# 05_SDRAM.net
KiCad netlist of a schematic drawn in Altium Designer
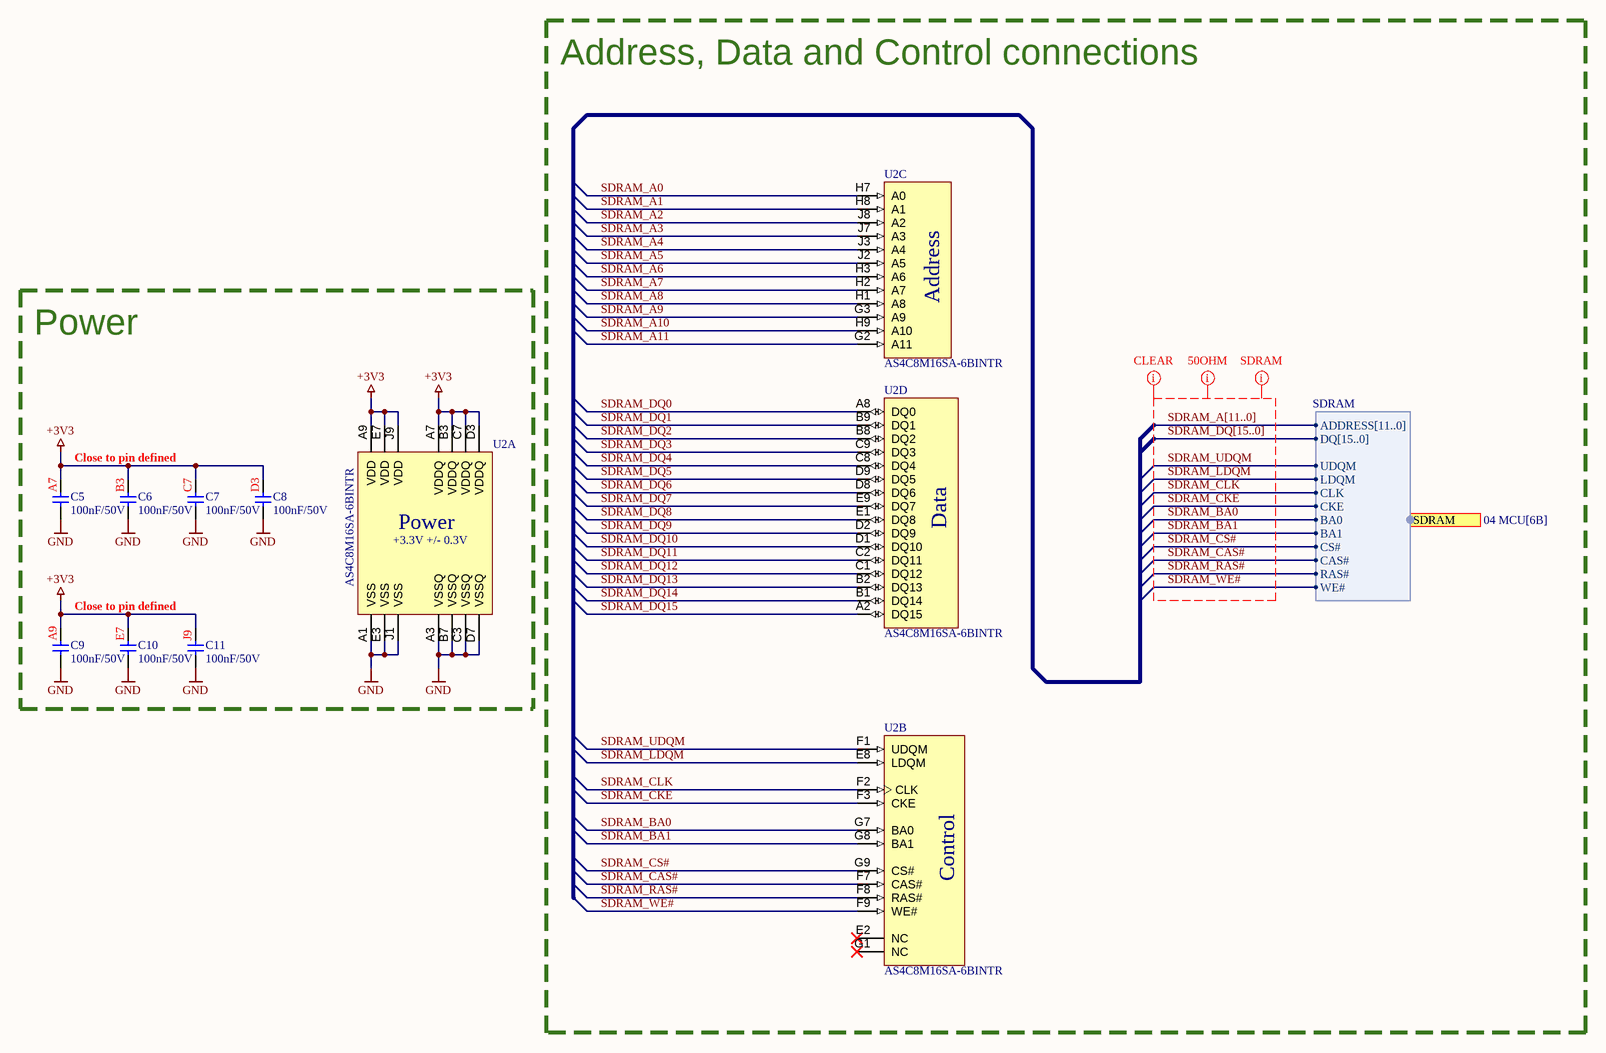
[diagram p0: 05 SDRAM.SchDoc]

(export (version "E")
  (design (tool "Eeschema 10.0.6"))
  (components
    (comp (ref "C5")
      (value "100nF/50V")
      (footprint "CAPC1005X06M-0402")
      (description "0.1 µF ±10% 50V Ceramic Capacitor X7R 0402 (1005 Metric)")
      (fields (field (name "MPN") "GRM155R71H104KE14D"))
      (libsource (lib "Symbol") (part "GRM155R71H104KE14D"))
    )
    (comp (ref "C6")
      (value "100nF/50V")
      (footprint "CAPC1005X06M-0402")
      (description "0.1 µF ±10% 50V Ceramic Capacitor X7R 0402 (1005 Metric)")
      (fields (field (name "MPN") "GRM155R71H104KE14D"))
      (libsource (lib "Symbol") (part "GRM155R71H104KE14D"))
    )
    (comp (ref "C7")
      (value "100nF/50V")
      (footprint "CAPC1005X06M-0402")
      (description "0.1 µF ±10% 50V Ceramic Capacitor X7R 0402 (1005 Metric)")
      (fields (field (name "MPN") "GRM155R71H104KE14D"))
      (libsource (lib "Symbol") (part "GRM155R71H104KE14D"))
    )
    (comp (ref "C8")
      (value "100nF/50V")
      (footprint "CAPC1005X06M-0402")
      (description "0.1 µF ±10% 50V Ceramic Capacitor X7R 0402 (1005 Metric)")
      (fields (field (name "MPN") "GRM155R71H104KE14D"))
      (libsource (lib "Symbol") (part "GRM155R71H104KE14D"))
    )
    (comp (ref "C9")
      (value "100nF/50V")
      (footprint "CAPC1005X06M-0402")
      (description "0.1 µF ±10% 50V Ceramic Capacitor X7R 0402 (1005 Metric)")
      (fields (field (name "MPN") "GRM155R71H104KE14D"))
      (libsource (lib "Symbol") (part "GRM155R71H104KE14D"))
    )
    (comp (ref "C10")
      (value "100nF/50V")
      (footprint "CAPC1005X06M-0402")
      (description "0.1 µF ±10% 50V Ceramic Capacitor X7R 0402 (1005 Metric)")
      (fields (field (name "MPN") "GRM155R71H104KE14D"))
      (libsource (lib "Symbol") (part "GRM155R71H104KE14D"))
    )
    (comp (ref "C11")
      (value "100nF/50V")
      (footprint "CAPC1005X06M-0402")
      (description "0.1 µF ±10% 50V Ceramic Capacitor X7R 0402 (1005 Metric)")
      (fields (field (name "MPN") "GRM155R71H104KE14D"))
      (libsource (lib "Symbol") (part "GRM155R71H104KE14D"))
    )
    (comp (ref "U2")
      (value "AS4C8M16SA-6BINTR")
      (footprint "TFBGA-54")
      (description "SDRAM Memory IC 128Mbit Parallel 166 MHz 5 ns 54-TFBGA (8x8)")
      (libsource (lib "Symbol") (part "AS4C8M16SA-6BINTR"))
    )
  )
  (nets
    (net (code "2") (name "+3V3") (class "Default")
      (node (ref "C10") (pin "2") (pinfunction "2_2") (pintype "passive"))
      (node (ref "C11") (pin "2") (pinfunction "2_2") (pintype "passive"))
      (node (ref "C5") (pin "2") (pinfunction "2_2") (pintype "passive"))
      (node (ref "C6") (pin "2") (pinfunction "2_2") (pintype "passive"))
      (node (ref "C7") (pin "2") (pinfunction "2_2") (pintype "passive"))
      (node (ref "C8") (pin "2") (pinfunction "2_2") (pintype "passive"))
      (node (ref "C9") (pin "2") (pinfunction "2_2") (pintype "passive"))
      (node (ref "U2") (pin "A7") (pinfunction "VDDQ_A7") (pintype "power_in"))
      (node (ref "U2") (pin "A9") (pinfunction "VDD_A9") (pintype "power_in"))
      (node (ref "U2") (pin "B3") (pinfunction "VDDQ_B3") (pintype "power_in"))
      (node (ref "U2") (pin "C7") (pinfunction "VDDQ_C7") (pintype "power_in"))
      (node (ref "U2") (pin "D3") (pinfunction "VDDQ_D3") (pintype "power_in"))
      (node (ref "U2") (pin "E7") (pinfunction "VDD_E7") (pintype "power_in"))
      (node (ref "U2") (pin "J9") (pinfunction "VDD_J9") (pintype "power_in"))
    )
    (net (code "3") (name "/SDRAM_A0") (class "Default")
      (node (ref "U2") (pin "H7") (pinfunction "A0_H7") (pintype "input"))
    )
    (net (code "4") (name "/SDRAM_A1") (class "Default")
      (node (ref "U2") (pin "H8") (pinfunction "A1_H8") (pintype "input"))
    )
    (net (code "5") (name "/SDRAM_A2") (class "Default")
      (node (ref "U2") (pin "J8") (pinfunction "A2_J8") (pintype "input"))
    )
    (net (code "6") (name "/SDRAM_A3") (class "Default")
      (node (ref "U2") (pin "J7") (pinfunction "A3_J7") (pintype "input"))
    )
    (net (code "7") (name "/SDRAM_A4") (class "Default")
      (node (ref "U2") (pin "J3") (pinfunction "A4_J3") (pintype "input"))
    )
    (net (code "8") (name "/SDRAM_A5") (class "Default")
      (node (ref "U2") (pin "J2") (pinfunction "A5_J2") (pintype "input"))
    )
    (net (code "9") (name "/SDRAM_A6") (class "Default")
      (node (ref "U2") (pin "H3") (pinfunction "A6_H3") (pintype "input"))
    )
    (net (code "10") (name "/SDRAM_A7") (class "Default")
      (node (ref "U2") (pin "H2") (pinfunction "A7_H2") (pintype "input"))
    )
    (net (code "11") (name "/SDRAM_A8") (class "Default")
      (node (ref "U2") (pin "H1") (pinfunction "A8_H1") (pintype "input"))
    )
    (net (code "12") (name "/SDRAM_A9") (class "Default")
      (node (ref "U2") (pin "G3") (pinfunction "A9_G3") (pintype "input"))
    )
    (net (code "13") (name "/SDRAM_A10") (class "Default")
      (node (ref "U2") (pin "H9") (pinfunction "A10_H9") (pintype "input"))
    )
    (net (code "14") (name "/SDRAM_A11") (class "Default")
      (node (ref "U2") (pin "G2") (pinfunction "A11_G2") (pintype "input"))
    )
    (net (code "15") (name "/SDRAM_BA0") (class "Default")
      (node (ref "U2") (pin "G7") (pinfunction "BA0_G7") (pintype "input"))
    )
    (net (code "16") (name "/SDRAM_BA1") (class "Default")
      (node (ref "U2") (pin "G8") (pinfunction "BA1_G8") (pintype "input"))
    )
    (net (code "17") (name "/SDRAM_CAS#") (class "Default")
      (node (ref "U2") (pin "F7") (pinfunction "CAS#_F7") (pintype "input"))
    )
    (net (code "18") (name "/SDRAM_CKE") (class "Default")
      (node (ref "U2") (pin "F3") (pinfunction "CKE_F3") (pintype "input"))
    )
    (net (code "19") (name "/SDRAM_CLK") (class "Default")
      (node (ref "U2") (pin "F2") (pinfunction "CLK_F2") (pintype "input"))
    )
    (net (code "20") (name "/SDRAM_CS#") (class "Default")
      (node (ref "U2") (pin "G9") (pinfunction "CS#_G9") (pintype "input"))
    )
    (net (code "21") (name "/SDRAM_DQ0") (class "Default")
      (node (ref "U2") (pin "A8") (pinfunction "DQ0_A8") (pintype "bidirectional"))
    )
    (net (code "22") (name "/SDRAM_DQ1") (class "Default")
      (node (ref "U2") (pin "B9") (pinfunction "DQ1_B9") (pintype "bidirectional"))
    )
    (net (code "23") (name "/SDRAM_DQ2") (class "Default")
      (node (ref "U2") (pin "B8") (pinfunction "DQ2_B8") (pintype "bidirectional"))
    )
    (net (code "24") (name "/SDRAM_DQ3") (class "Default")
      (node (ref "U2") (pin "C9") (pinfunction "DQ3_C9") (pintype "bidirectional"))
    )
    (net (code "25") (name "/SDRAM_DQ4") (class "Default")
      (node (ref "U2") (pin "C8") (pinfunction "DQ4_C8") (pintype "bidirectional"))
    )
    (net (code "26") (name "/SDRAM_DQ5") (class "Default")
      (node (ref "U2") (pin "D9") (pinfunction "DQ5_D9") (pintype "bidirectional"))
    )
    (net (code "27") (name "/SDRAM_DQ6") (class "Default")
      (node (ref "U2") (pin "D8") (pinfunction "DQ6_D8") (pintype "bidirectional"))
    )
    (net (code "28") (name "/SDRAM_DQ7") (class "Default")
      (node (ref "U2") (pin "E9") (pinfunction "DQ7_E9") (pintype "bidirectional"))
    )
    (net (code "29") (name "/SDRAM_DQ8") (class "Default")
      (node (ref "U2") (pin "E1") (pinfunction "DQ8_E1") (pintype "bidirectional"))
    )
    (net (code "30") (name "/SDRAM_DQ9") (class "Default")
      (node (ref "U2") (pin "D2") (pinfunction "DQ9_D2") (pintype "bidirectional"))
    )
    (net (code "31") (name "/SDRAM_DQ10") (class "Default")
      (node (ref "U2") (pin "D1") (pinfunction "DQ10_D1") (pintype "bidirectional"))
    )
    (net (code "32") (name "/SDRAM_DQ11") (class "Default")
      (node (ref "U2") (pin "C2") (pinfunction "DQ11_C2") (pintype "bidirectional"))
    )
    (net (code "33") (name "/SDRAM_DQ12") (class "Default")
      (node (ref "U2") (pin "C1") (pinfunction "DQ12_C1") (pintype "bidirectional"))
    )
    (net (code "34") (name "/SDRAM_DQ13") (class "Default")
      (node (ref "U2") (pin "B2") (pinfunction "DQ13_B2") (pintype "bidirectional"))
    )
    (net (code "35") (name "/SDRAM_DQ14") (class "Default")
      (node (ref "U2") (pin "B1") (pinfunction "DQ14_B1") (pintype "bidirectional"))
    )
    (net (code "36") (name "/SDRAM_DQ15") (class "Default")
      (node (ref "U2") (pin "A2") (pinfunction "DQ15_A2") (pintype "bidirectional"))
    )
    (net (code "38") (name "/SDRAM_LDQM") (class "Default")
      (node (ref "U2") (pin "E8") (pinfunction "LDQM_E8") (pintype "input"))
    )
    (net (code "39") (name "/SDRAM_RAS#") (class "Default")
      (node (ref "U2") (pin "F8") (pinfunction "RAS#_F8") (pintype "input"))
    )
    (net (code "40") (name "/SDRAM_UDQM") (class "Default")
      (node (ref "U2") (pin "F1") (pinfunction "UDQM_F1") (pintype "input"))
    )
    (net (code "41") (name "/SDRAM_WE#") (class "Default")
      (node (ref "U2") (pin "F9") (pinfunction "WE#_F9") (pintype "input"))
    )
    (net (code "44") (name "GND") (class "Default")
      (node (ref "C10") (pin "1") (pinfunction "1_1") (pintype "passive"))
      (node (ref "C11") (pin "1") (pinfunction "1_1") (pintype "passive"))
      (node (ref "C5") (pin "1") (pinfunction "1_1") (pintype "passive"))
      (node (ref "C6") (pin "1") (pinfunction "1_1") (pintype "passive"))
      (node (ref "C7") (pin "1") (pinfunction "1_1") (pintype "passive"))
      (node (ref "C8") (pin "1") (pinfunction "1_1") (pintype "passive"))
      (node (ref "C9") (pin "1") (pinfunction "1_1") (pintype "passive"))
      (node (ref "U2") (pin "A1") (pinfunction "VSS_A1") (pintype "power_in"))
      (node (ref "U2") (pin "A3") (pinfunction "VSSQ_A3") (pintype "power_in"))
      (node (ref "U2") (pin "B7") (pinfunction "VSSQ_B7") (pintype "power_in"))
      (node (ref "U2") (pin "C3") (pinfunction "VSSQ_C3") (pintype "power_in"))
      (node (ref "U2") (pin "D7") (pinfunction "VSSQ_D7") (pintype "power_in"))
      (node (ref "U2") (pin "E3") (pinfunction "VSS_E3") (pintype "power_in"))
      (node (ref "U2") (pin "J1") (pinfunction "VSS_J1") (pintype "power_in"))
    )
    (net (code "45") (name "unconnected-(U2B-NC-PadE2)") (class "Default")
      (node (ref "U2") (pin "E2") (pinfunction "NC_E2") (pintype "passive+no_connect"))
    )
    (net (code "46") (name "unconnected-(U2B-NC-PadG1)") (class "Default")
      (node (ref "U2") (pin "G1") (pinfunction "NC_G1") (pintype "passive+no_connect"))
    )
  )
)
